# EtherCATConnectors.net
KiCad netlist of a schematic drawn in Altium Designer
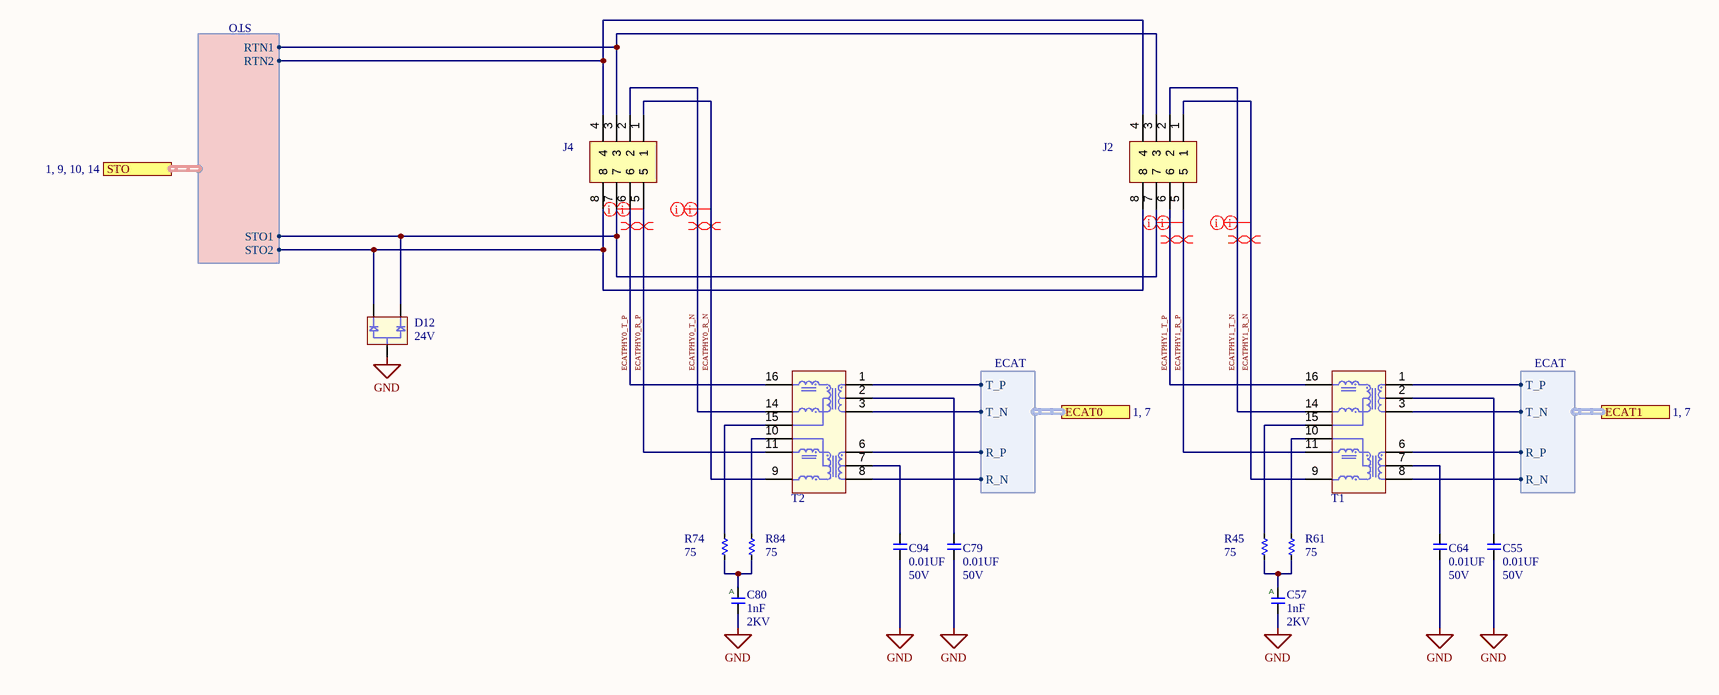
[diagram p0: EtherCATConnectors.SchDoc]

(export (version "E")
  (design (tool "Eeschema 10.0.6"))
  (components
    (comp (ref "C55")
      (value "0.01UF")
      (footprint "C0402")
      (description "CAP, CER, X7R, 0.01uF, 50V, 20%, 0402, 0.56mm T")
      (fields
        (field (name "MFG") "KEMET")
        (field (name "VOLTAGE") "50V")
        (field (name "Comment") "__Template_Cap")
      )
      (libsource (lib "AltiumReleaseLibDB") (part "__Template_Cap"))
    )
    (comp (ref "C57")
      (value "1nF")
      (footprint "C1210")
      (description "CAP, CER, X7S, 1000PF, 2KV, 10%, 1210")
      (fields
        (field (name "MFG") "TDK")
        (field (name "VOLTAGE") "2KV")
        (field (name "Comment") "__Template_Cap_Auto")
      )
      (libsource (lib "AltiumReleaseLibDB") (part "__Template_Cap_Auto"))
    )
    (comp (ref "C64")
      (value "0.01UF")
      (footprint "C0402")
      (description "CAP, CER, X7R, 0.01uF, 50V, 20%, 0402, 0.56mm T")
      (fields
        (field (name "MFG") "KEMET")
        (field (name "VOLTAGE") "50V")
        (field (name "Comment") "__Template_Cap")
      )
      (libsource (lib "AltiumReleaseLibDB") (part "__Template_Cap"))
    )
    (comp (ref "C79")
      (value "0.01UF")
      (footprint "C0402")
      (description "CAP, CER, X7R, 0.01uF, 50V, 20%, 0402, 0.56mm T")
      (fields
        (field (name "MFG") "KEMET")
        (field (name "VOLTAGE") "50V")
        (field (name "Comment") "__Template_Cap")
      )
      (libsource (lib "AltiumReleaseLibDB") (part "__Template_Cap"))
    )
    (comp (ref "C80")
      (value "1nF")
      (footprint "C1210")
      (description "CAP, CER, X7S, 1000PF, 2KV, 10%, 1210")
      (fields
        (field (name "MFG") "TDK")
        (field (name "VOLTAGE") "2KV")
        (field (name "Comment") "__Template_Cap_Auto")
      )
      (libsource (lib "AltiumReleaseLibDB") (part "__Template_Cap_Auto"))
    )
    (comp (ref "C94")
      (value "0.01UF")
      (footprint "C0402")
      (description "CAP, CER, X7R, 0.01uF, 50V, 20%, 0402, 0.56mm T")
      (fields
        (field (name "MFG") "KEMET")
        (field (name "VOLTAGE") "50V")
        (field (name "Comment") "__Template_Cap")
      )
      (libsource (lib "AltiumReleaseLibDB") (part "__Template_Cap"))
    )
    (comp (ref "D12")
      (value "24V")
      (footprint "3SOT23")
      (description "DIODE, TVS, UNIDIR, DUAL, 24VRWM, 26VBR, 41VCL, SOT-23-3")
      (fields (field (name "MFG") "Infineon Technologies"))
      (libsource (lib "AltiumReleaseLibDB") (part "DIODE_TVS_ESD24VS2UE6327HTSA1"))
    )
    (comp (ref "J2")
      (value "MOLEX_2X4_NANOFIT_1053141308")
      (footprint "MOLEX_1053141308")
      (description "CONN HEADER R/A 8POS 2.5MM")
      (fields (field (name "MFG") "Molex"))
      (libsource (lib "Cortes_Gebru_v05_Rev03") (part "MOLEX_2X4_NANOFIT_1053141308"))
    )
    (comp (ref "J4")
      (value "MOLEX_2X4_NANOFIT_1053141308")
      (footprint "MOLEX_1053141308")
      (description "CONN HEADER R/A 8POS 2.5MM")
      (fields (field (name "MFG") "Molex"))
      (libsource (lib "Cortes_Gebru_v05_Rev03") (part "MOLEX_2X4_NANOFIT_1053141308"))
    )
    (comp (ref "R45")
      (value "75")
      (footprint "R0402")
      (description "RES, 75, 1%, 1/16W, 0402")
      (fields (field (name "MFG") "YAGEO"))
      (libsource (lib "AltiumReleaseLibDB") (part "__Template_Resistor"))
    )
    (comp (ref "R61")
      (value "75")
      (footprint "R0402")
      (description "RES, 75, 1%, 1/16W, 0402")
      (fields (field (name "MFG") "YAGEO"))
      (libsource (lib "AltiumReleaseLibDB") (part "__Template_Resistor"))
    )
    (comp (ref "R74")
      (value "75")
      (footprint "R0402")
      (description "RES, 75, 1%, 1/16W, 0402")
      (fields (field (name "MFG") "YAGEO"))
      (libsource (lib "AltiumReleaseLibDB") (part "__Template_Resistor"))
    )
    (comp (ref "R84")
      (value "75")
      (footprint "R0402")
      (description "RES, 75, 1%, 1/16W, 0402")
      (fields (field (name "MFG") "YAGEO"))
      (libsource (lib "AltiumReleaseLibDB") (part "__Template_Resistor"))
    )
    (comp (ref "T1")
      (value "PULSE_H1102NL")
      (footprint "PULSE_HXXXX")
      (description "Telecom Transformer 2(1:1) 0.65Ohm Prim. DCR 0.65Ohm Sec. DCR 16 Terminal Gull Wing SMD")
      (fields (field (name "MFG") "Pulse Electronics"))
      (libsource (lib "MiscSch1") (part "PULSE_H1102NL"))
    )
    (comp (ref "T2")
      (value "PULSE_H1102NL")
      (footprint "PULSE_HXXXX")
      (description "Telecom Transformer 2(1:1) 0.65Ohm Prim. DCR 0.65Ohm Sec. DCR 16 Terminal Gull Wing SMD")
      (fields (field (name "MFG") "Pulse Electronics"))
      (libsource (lib "MiscSch1") (part "PULSE_H1102NL"))
    )
  )
  (nets
    (net (code "3") (name "/ECATPHY0_R_N") (class "Default")
      (node (ref "J4") (pin "1") (pinfunction "1_1") (pintype "passive"))
      (node (ref "T2") (pin "9") (pintype "passive"))
    )
    (net (code "4") (name "/ECATPHY0_R_P") (class "Default")
      (node (ref "J4") (pin "5") (pinfunction "5_5") (pintype "passive"))
      (node (ref "T2") (pin "11") (pintype "passive"))
    )
    (net (code "5") (name "/ECATPHY0_T_N") (class "Default")
      (node (ref "J4") (pin "2") (pinfunction "2_2") (pintype "passive"))
      (node (ref "T2") (pin "14") (pintype "passive"))
    )
    (net (code "6") (name "/ECATPHY0_T_P") (class "Default")
      (node (ref "J4") (pin "6") (pinfunction "6_6") (pintype "passive"))
      (node (ref "T2") (pin "16") (pintype "passive"))
    )
    (net (code "7") (name "/ECATPHY1_R_N") (class "Default")
      (node (ref "J2") (pin "1") (pinfunction "1_1") (pintype "passive"))
      (node (ref "T1") (pin "9") (pintype "passive"))
    )
    (net (code "8") (name "/ECATPHY1_R_P") (class "Default")
      (node (ref "J2") (pin "5") (pinfunction "5_5") (pintype "passive"))
      (node (ref "T1") (pin "11") (pintype "passive"))
    )
    (net (code "9") (name "/ECATPHY1_T_N") (class "Default")
      (node (ref "J2") (pin "2") (pinfunction "2_2") (pintype "passive"))
      (node (ref "T1") (pin "14") (pintype "passive"))
    )
    (net (code "10") (name "/ECATPHY1_T_P") (class "Default")
      (node (ref "J2") (pin "6") (pinfunction "6_6") (pintype "passive"))
      (node (ref "T1") (pin "16") (pintype "passive"))
    )
    (net (code "11") (name "/RTN1") (class "Default")
      (node (ref "J2") (pin "3") (pinfunction "3_3") (pintype "passive"))
      (node (ref "J4") (pin "3") (pinfunction "3_3") (pintype "passive"))
    )
    (net (code "12") (name "/RTN2") (class "Default")
      (node (ref "J2") (pin "4") (pinfunction "4_4") (pintype "passive"))
      (node (ref "J4") (pin "4") (pinfunction "4_4") (pintype "passive"))
    )
    (net (code "13") (name "/STO1") (class "Default")
      (node (ref "D12") (pin "1") (pinfunction "1_1") (pintype "passive"))
      (node (ref "J2") (pin "7") (pinfunction "7_7") (pintype "passive"))
      (node (ref "J4") (pin "7") (pinfunction "7_7") (pintype "passive"))
    )
    (net (code "14") (name "/STO2") (class "Default")
      (node (ref "D12") (pin "2") (pinfunction "2_2") (pintype "passive"))
      (node (ref "J2") (pin "8") (pinfunction "8_8") (pintype "passive"))
      (node (ref "J4") (pin "8") (pinfunction "8_8") (pintype "passive"))
    )
    (net (code "17") (name "GND") (class "Default")
      (node (ref "C55") (pin "2") (pintype "passive"))
      (node (ref "C57") (pin "2") (pintype "passive"))
      (node (ref "C64") (pin "2") (pintype "passive"))
      (node (ref "C79") (pin "2") (pintype "passive"))
      (node (ref "C80") (pin "2") (pintype "passive"))
      (node (ref "C94") (pin "2") (pintype "passive"))
      (node (ref "D12") (pin "3") (pinfunction "3_3") (pintype "passive"))
    )
    (net (code "18") (name "Net-(C55-Pad1)") (class "Default")
      (node (ref "C55") (pin "1") (pintype "passive"))
      (node (ref "T1") (pin "2") (pintype "passive"))
    )
    (net (code "19") (name "Net-(C57-Pad1)") (class "Default")
      (node (ref "C57") (pin "1") (pintype "passive"))
      (node (ref "R45") (pin "1") (pintype "passive"))
      (node (ref "R61") (pin "1") (pintype "passive"))
    )
    (net (code "20") (name "Net-(C64-Pad1)") (class "Default")
      (node (ref "C64") (pin "1") (pintype "passive"))
      (node (ref "T1") (pin "7") (pintype "passive"))
    )
    (net (code "21") (name "Net-(C79-Pad1)") (class "Default")
      (node (ref "C79") (pin "1") (pintype "passive"))
      (node (ref "T2") (pin "2") (pintype "passive"))
    )
    (net (code "22") (name "Net-(C80-Pad1)") (class "Default")
      (node (ref "C80") (pin "1") (pintype "passive"))
      (node (ref "R74") (pin "1") (pintype "passive"))
      (node (ref "R84") (pin "1") (pintype "passive"))
    )
    (net (code "23") (name "Net-(C94-Pad1)") (class "Default")
      (node (ref "C94") (pin "1") (pintype "passive"))
      (node (ref "T2") (pin "7") (pintype "passive"))
    )
    (net (code "24") (name "Net-(R45-Pad2)") (class "Default")
      (node (ref "R45") (pin "2") (pintype "passive"))
      (node (ref "T1") (pin "15") (pintype "passive"))
    )
    (net (code "25") (name "Net-(R61-Pad2)") (class "Default")
      (node (ref "R61") (pin "2") (pintype "passive"))
      (node (ref "T1") (pin "10") (pintype "passive"))
    )
    (net (code "26") (name "Net-(R74-Pad2)") (class "Default")
      (node (ref "R74") (pin "2") (pintype "passive"))
      (node (ref "T2") (pin "15") (pintype "passive"))
    )
    (net (code "27") (name "Net-(R84-Pad2)") (class "Default")
      (node (ref "R84") (pin "2") (pintype "passive"))
      (node (ref "T2") (pin "10") (pintype "passive"))
    )
    (net (code "28") (name "unconnected-(T1-Pad1)") (class "Default")
      (node (ref "T1") (pin "1") (pintype "passive"))
    )
    (net (code "29") (name "unconnected-(T1-Pad3)") (class "Default")
      (node (ref "T1") (pin "3") (pintype "passive"))
    )
    (net (code "30") (name "unconnected-(T1-Pad6)") (class "Default")
      (node (ref "T1") (pin "6") (pintype "passive"))
    )
    (net (code "31") (name "unconnected-(T1-Pad8)") (class "Default")
      (node (ref "T1") (pin "8") (pintype "passive"))
    )
    (net (code "32") (name "unconnected-(T2-Pad1)") (class "Default")
      (node (ref "T2") (pin "1") (pintype "passive"))
    )
    (net (code "33") (name "unconnected-(T2-Pad3)") (class "Default")
      (node (ref "T2") (pin "3") (pintype "passive"))
    )
    (net (code "34") (name "unconnected-(T2-Pad6)") (class "Default")
      (node (ref "T2") (pin "6") (pintype "passive"))
    )
    (net (code "35") (name "unconnected-(T2-Pad8)") (class "Default")
      (node (ref "T2") (pin "8") (pintype "passive"))
    )
  )
)
